# 0226-FETz-0126-carrier.net
KiCad netlist of a schematic drawn in EAGLE
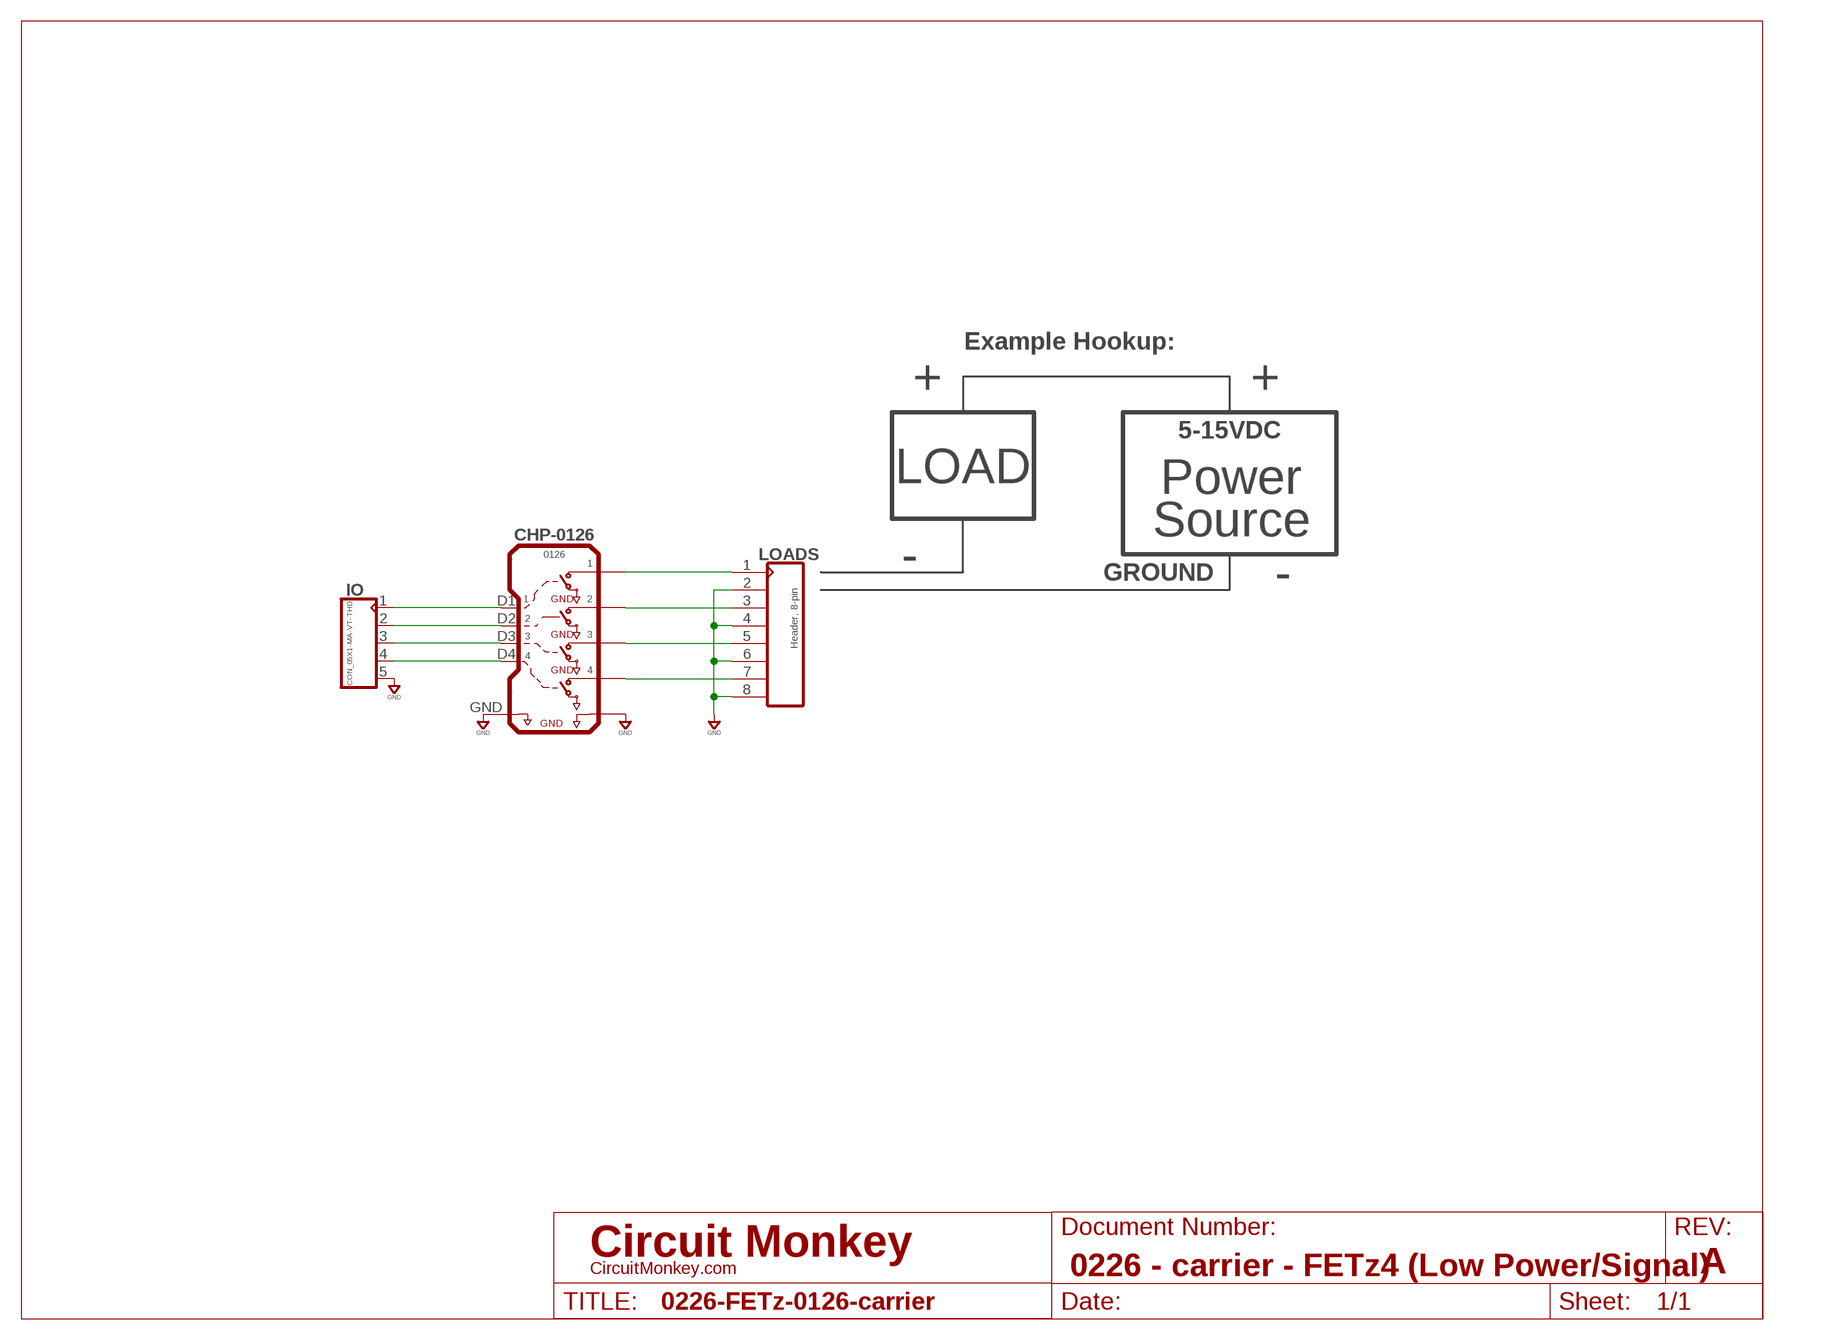
[diagram p0: schematic, sheet 1]

(export (version "E")
  (design (tool "Eeschema 10.0.6"))
  (components
    (comp (ref "CHP-0126")
      (value "0126")
      (footprint "eagle-import:0126A")
      (fields (field (name "MFR") "Circuit Monkey") (field (name "MPN") "0126A"))
      (libsource (lib "eagle-import") (part "0126REV-A"))
    )
    (comp (ref "IO")
      (value "CON_05X1-MA-VT-THD")
      (footprint "eagle-import:MA05X1-VT-THD")
      (libsource (lib "eagle-import") (part "CON_05X1-MA-VT-THD"))
    )
    (comp (ref "LOADS")
      (value "Header, 8-pin")
      (footprint "eagle-import:MA08X1-VT-THD")
      (libsource (lib "eagle-import") (part "CON_08X1-VT-THD"))
    )
  )
  (nets
    (net (code "1") (name "GND") (class "Default")
      (node (ref "CHP-0126") (pin "GND") (pinfunction "GND_GND") (pintype "bidirectional"))
      (node (ref "CHP-0126") (pin "GNDL") (pinfunction "GND2_GNDL") (pintype "bidirectional"))
      (node (ref "IO") (pin "5") (pinfunction "5_5") (pintype "passive"))
      (node (ref "LOADS") (pin "2") (pinfunction "2_2") (pintype "passive"))
      (node (ref "LOADS") (pin "4") (pinfunction "4_4") (pintype "passive"))
      (node (ref "LOADS") (pin "6") (pinfunction "6_6") (pintype "passive"))
      (node (ref "LOADS") (pin "8") (pinfunction "8_8") (pintype "passive"))
    )
    (net (code "2") (name "Net-(CHP-0126-1)") (class "Default")
      (node (ref "CHP-0126") (pin "D1") (pinfunction "1_D1") (pintype "bidirectional"))
      (node (ref "IO") (pin "1") (pinfunction "1_1") (pintype "passive"))
    )
    (net (code "3") (name "Net-(CHP-0126-2)") (class "Default")
      (node (ref "CHP-0126") (pin "D2") (pinfunction "2_D2") (pintype "bidirectional"))
      (node (ref "IO") (pin "2") (pinfunction "2_2") (pintype "passive"))
    )
    (net (code "4") (name "Net-(CHP-0126-3)") (class "Default")
      (node (ref "CHP-0126") (pin "D3") (pinfunction "3_D3") (pintype "bidirectional"))
      (node (ref "IO") (pin "3") (pinfunction "3_3") (pintype "passive"))
    )
    (net (code "5") (name "Net-(CHP-0126-4)") (class "Default")
      (node (ref "CHP-0126") (pin "D4") (pinfunction "4_D4") (pintype "bidirectional"))
      (node (ref "IO") (pin "4") (pinfunction "4_4") (pintype "passive"))
    )
    (net (code "6") (name "Net-(CHP-0126-PadL1)") (class "Default")
      (node (ref "CHP-0126") (pin "L1") (pinfunction "L1_L1") (pintype "bidirectional"))
      (node (ref "LOADS") (pin "1") (pinfunction "1_1") (pintype "passive"))
    )
    (net (code "7") (name "Net-(CHP-0126-PadL2)") (class "Default")
      (node (ref "CHP-0126") (pin "L2") (pinfunction "L2_L2") (pintype "bidirectional"))
      (node (ref "LOADS") (pin "3") (pinfunction "3_3") (pintype "passive"))
    )
    (net (code "8") (name "Net-(CHP-0126-PadL3)") (class "Default")
      (node (ref "CHP-0126") (pin "L3") (pinfunction "L3_L3") (pintype "bidirectional"))
      (node (ref "LOADS") (pin "5") (pinfunction "5_5") (pintype "passive"))
    )
    (net (code "9") (name "Net-(CHP-0126-PadL4)") (class "Default")
      (node (ref "CHP-0126") (pin "L4") (pinfunction "L4_L4") (pintype "bidirectional"))
      (node (ref "LOADS") (pin "7") (pinfunction "7_7") (pintype "passive"))
    )
  )
)
